# uMultimeter_ExpProbeA_Sch.net
KiCad netlist of a schematic drawn in Altium Designer
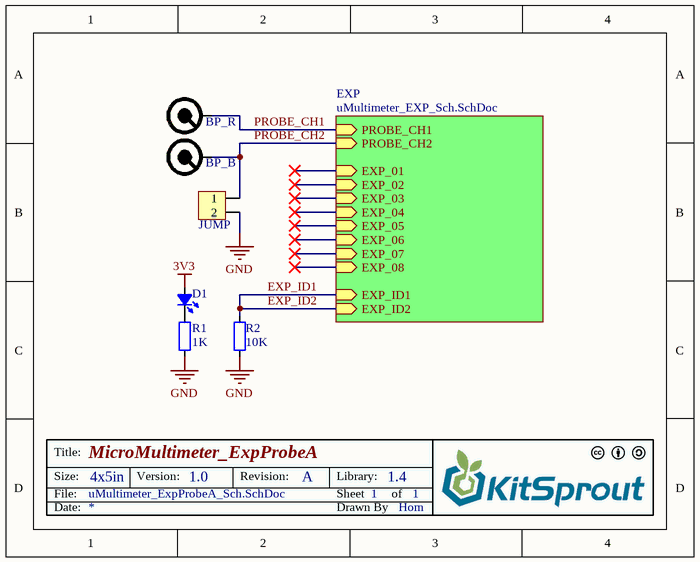
[diagram p0: uMultimeter_ExpProbeA_Sch.SchDoc]

(export (version "E")
  (design (tool "Eeschema 10.0.6"))
  (components
    (comp (ref "BP_B")
      (value "BananaPlugs")
      (footprint "PCB_ConnectorCable:BananaPlugs_Black")
      (libsource (lib "SCH_Connector") (part "BananaPlugs"))
    )
    (comp (ref "BP_R")
      (value "BananaPlugs")
      (footprint "PCB_ConnectorCable:BananaPlugs_Red")
      (libsource (lib "SCH_Connector") (part "BananaPlugs"))
    )
    (comp (ref "D1")
      (value "LED_0805")
      (footprint "PCB_ActiveLED:LED_0805_BLUE")
      (description "LED")
      (libsource (lib "SCH_Active") (part "LED_0805"))
    )
    (comp (ref "JUMP")
      (value "HDR1x2_2.54")
      (footprint "PCB_ConnectorHDR:HDR1X2_2.54_180")
      (description "Header")
      (libsource (lib "SCH_ConnectorHDR") (part "HDR1x2_2.54T"))
    )
    (comp (ref "R1")
      (value "1K")
      (footprint "PCB_PassiveRes:RES_0603")
      (description "Resistor")
      (fields (field (name "Comment") "Res_0603"))
      (libsource (lib "SCH_Passive") (part "Res_0603"))
    )
    (comp (ref "R2")
      (value "10K")
      (footprint "PCB_PassiveRes:RES_0603")
      (description "Resistor")
      (fields (field (name "Comment") "Res_0603"))
      (libsource (lib "") (part "Res_0603_1"))
    )
  )
  (nets
    (net (code "9") (name "/EXP_ID1") (class "Default")
      (node (ref "R2") (pin "2") (pinfunction "2_2") (pintype "passive"))
    )
    (net (code "10") (name "/PROBE_CH1") (class "Default")
      (node (ref "BP_R") (pin "1") (pinfunction "1_1") (pintype "passive"))
    )
    (net (code "11") (name "/PROBE_CH2") (class "Default")
      (node (ref "BP_B") (pin "1") (pinfunction "1_1") (pintype "passive"))
      (node (ref "JUMP") (pin "1") (pinfunction "1_1") (pintype "passive"))
    )
    (net (code "12") (name "3V3") (class "Default")
      (node (ref "D1") (pin "1") (pinfunction "A_1") (pintype "passive"))
    )
    (net (code "13") (name "GND") (class "Default")
      (node (ref "JUMP") (pin "2") (pinfunction "2_2") (pintype "passive"))
      (node (ref "R1") (pin "2") (pinfunction "2_2") (pintype "passive"))
      (node (ref "R2") (pin "1") (pinfunction "1_1") (pintype "passive"))
    )
    (net (code "14") (name "Net-(D1-K)") (class "Default")
      (node (ref "D1") (pin "2") (pinfunction "K_2") (pintype "passive"))
      (node (ref "R1") (pin "1") (pinfunction "1_1") (pintype "passive"))
    )
  )
)
